# SCH_Smart_Parking_IoT_2023-05-15_2.net
KiCad netlist of a schematic drawn in EasyEDA
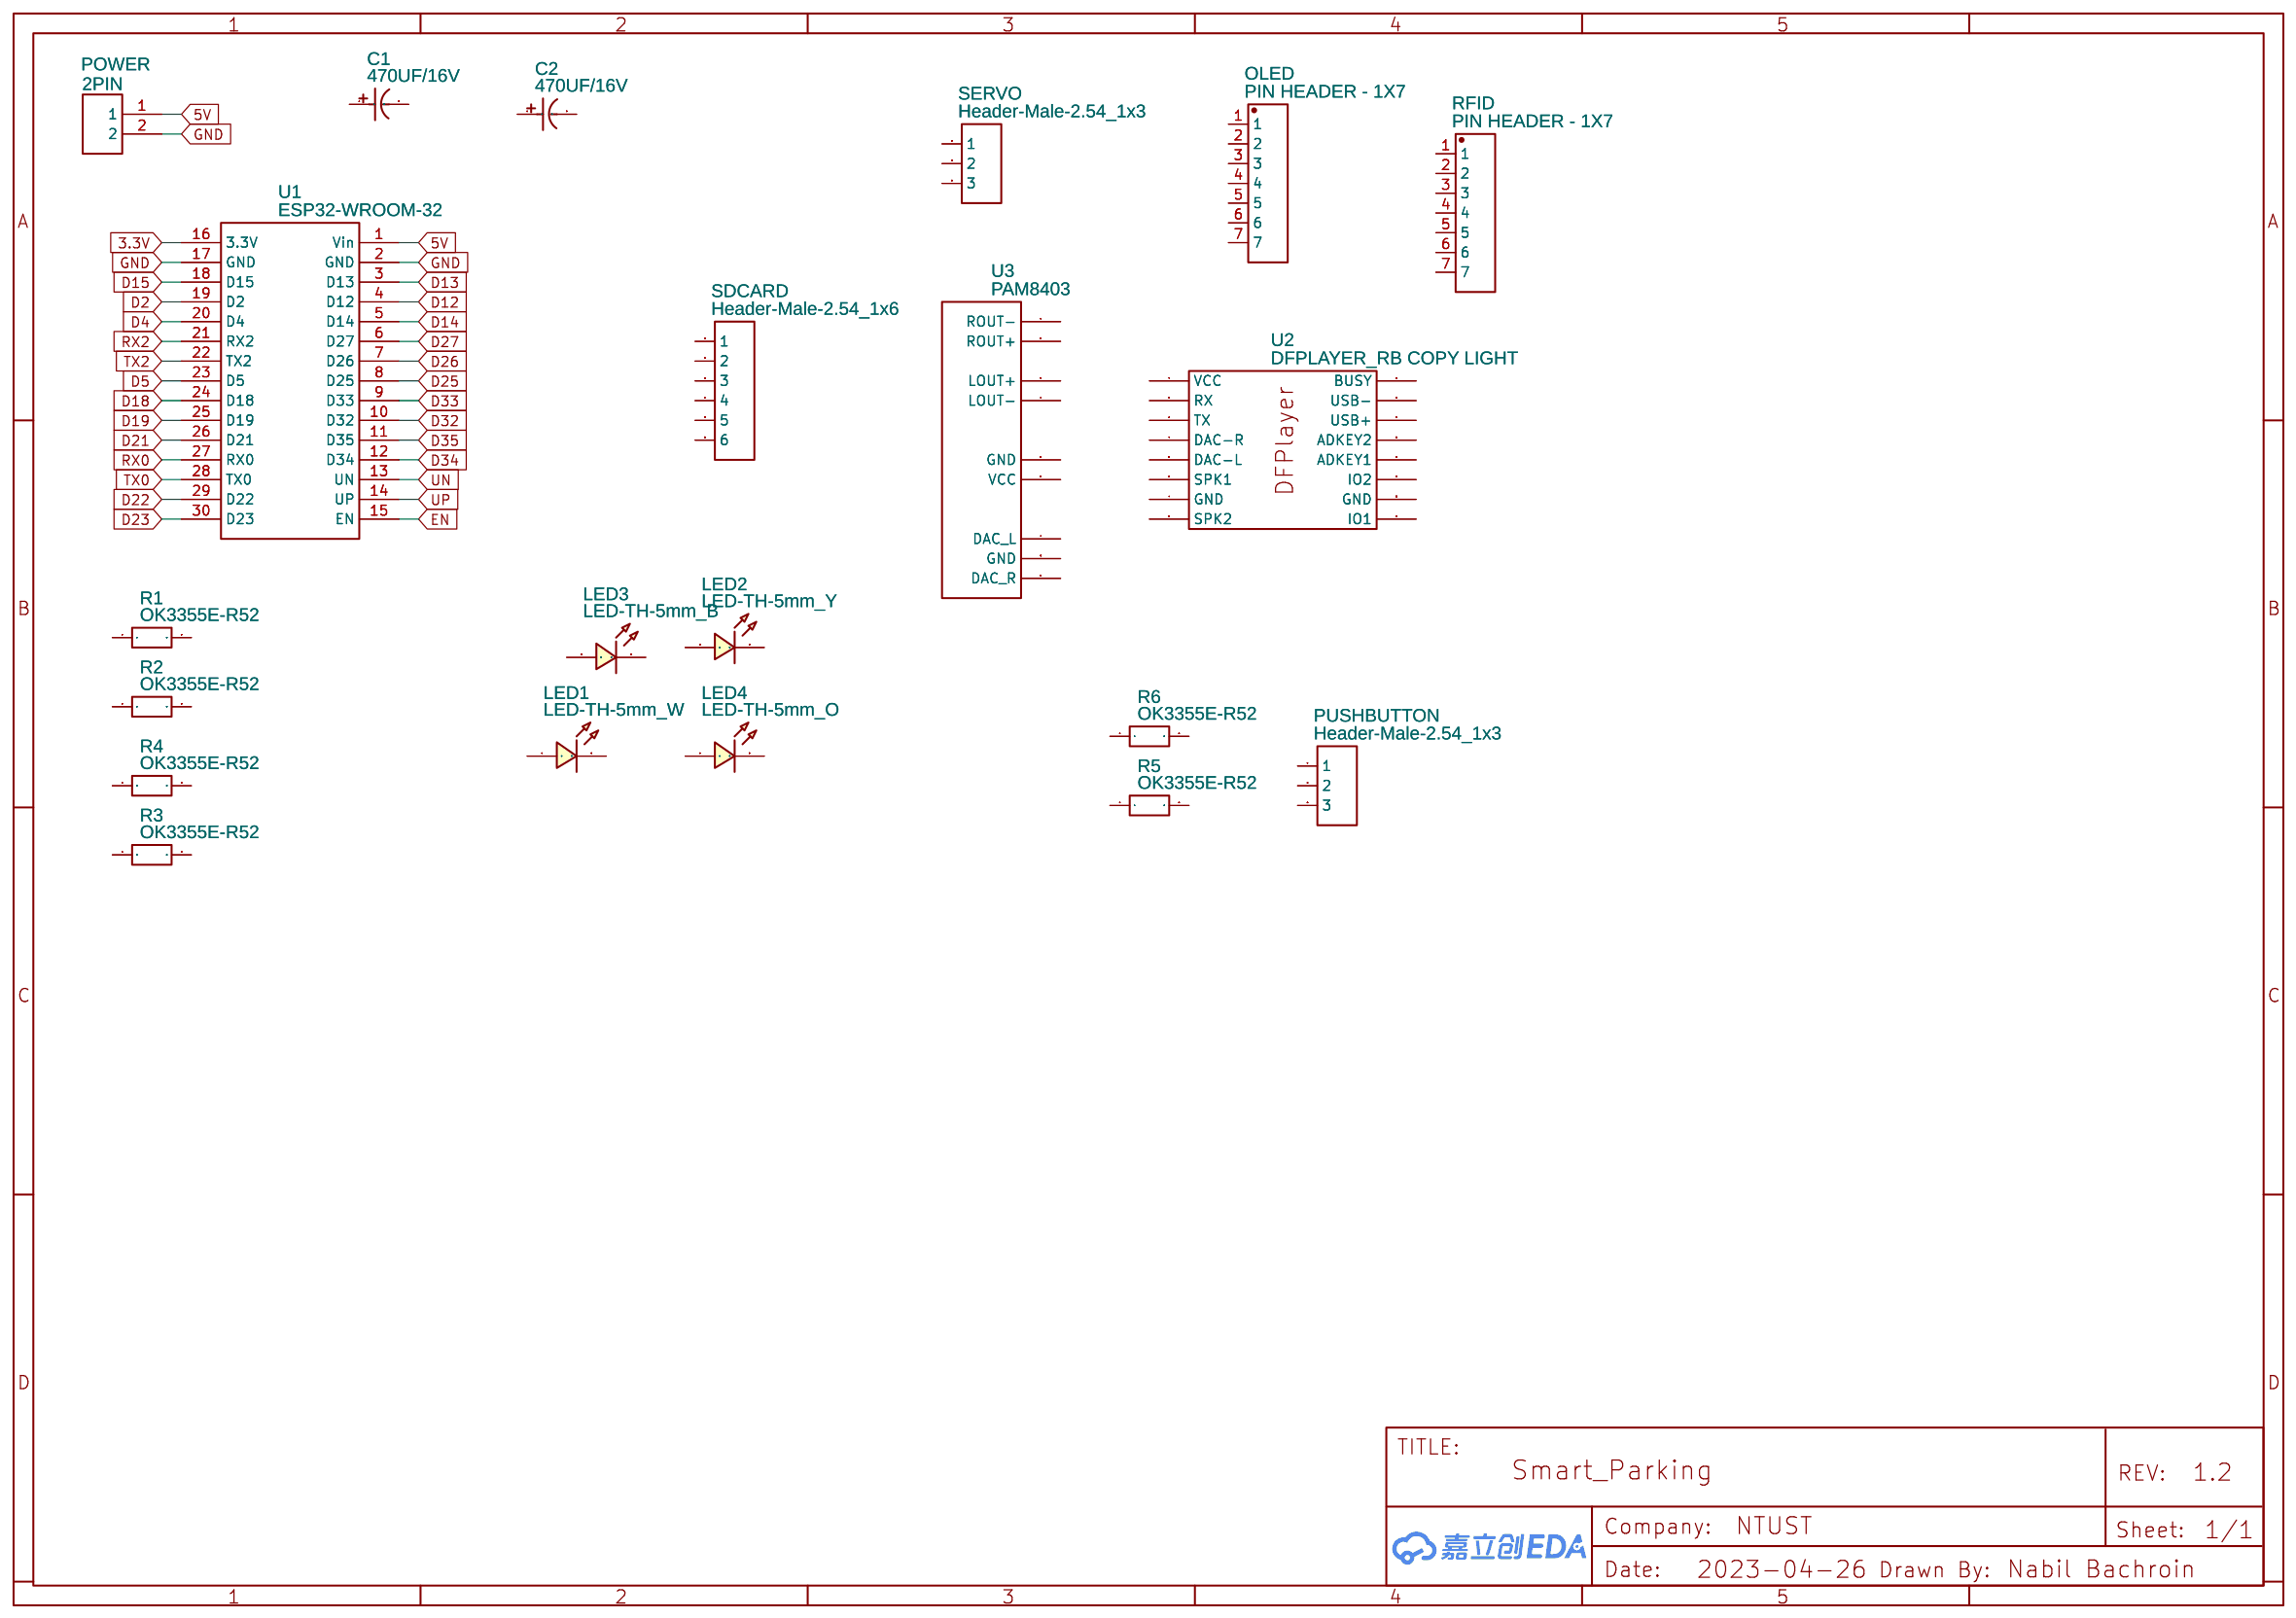
[diagram p0: schematic sheet]

(export (version "E")
  (design (tool "Eeschema 10.0.6"))
  (components
    (comp (ref "C1")
      (value "470UF/16V")
      (fields
        (field (name "BOM_Manufacturer Part") "470uF/16V")
        (field (name "BOM_Supplier Part") "C9900008131")
      )
      (libsource (lib "") (part "470UF/16V"))
    )
    (comp (ref "C2")
      (value "470UF/16V")
      (fields
        (field (name "BOM_Manufacturer Part") "470uF/16V")
        (field (name "BOM_Supplier Part") "C9900008131")
      )
      (libsource (lib "") (part "470UF/16V"))
    )
    (comp (ref "LED1") (value "LED-TH-5mm_W") (libsource (lib "") (part "LED-TH-5mm_W")))
    (comp (ref "LED2") (value "LED-TH-5mm_Y") (libsource (lib "") (part "LED-TH-5mm_Y")))
    (comp (ref "LED3") (value "LED-TH-5mm_B") (libsource (lib "") (part "LED-TH-5mm_B")))
    (comp (ref "LED4") (value "LED-TH-5mm_O") (libsource (lib "") (part "LED-TH-5mm_O")))
    (comp (ref "OLED") (value "PIN HEADER - 1X7") (libsource (lib "") (part "PIN HEADER - 1X7_1")))
    (comp (ref "POWER")
      (value "2PIN")
      (fields (field (name "BOM_Manufacturer Part") "Pin_Header_2"))
      (libsource (lib "") (part "2PIN"))
    )
    (comp (ref "PUSHBUTTON")
      (value "Header-Male-2.54_1x3")
      (fields (field (name "BOM_Manufacturer Part") "2.54-1*3P针") (field (name "BOM_Supplier Part") "C49257"))
      (libsource (lib "") (part "Header-Male-2.54_1x3"))
    )
    (comp (ref "R1")
      (value "OK3355E-R52")
      (fields (field (name "BOM_Supplier Part") "C3522642"))
      (libsource (lib "") (part "OK3355E-R52"))
    )
    (comp (ref "R2")
      (value "OK3355E-R52")
      (fields (field (name "BOM_Supplier Part") "C3522642"))
      (libsource (lib "") (part "OK3355E-R52"))
    )
    (comp (ref "R3")
      (value "OK3355E-R52")
      (fields (field (name "BOM_Supplier Part") "C3522642"))
      (libsource (lib "") (part "OK3355E-R52"))
    )
    (comp (ref "R4")
      (value "OK3355E-R52")
      (fields (field (name "BOM_Supplier Part") "C3522642"))
      (libsource (lib "") (part "OK3355E-R52"))
    )
    (comp (ref "R5")
      (value "OK3355E-R52")
      (fields (field (name "BOM_Supplier Part") "C3522642"))
      (libsource (lib "") (part "OK3355E-R52"))
    )
    (comp (ref "R6")
      (value "OK3355E-R52")
      (fields (field (name "BOM_Supplier Part") "C3522642"))
      (libsource (lib "") (part "OK3355E-R52"))
    )
    (comp (ref "RFID") (value "PIN HEADER - 1X7") (libsource (lib "") (part "PIN HEADER - 1X7")))
    (comp (ref "SDCARD")
      (value "Header-Male-2.54_1x6")
      (fields
        (field (name "BOM_Manufacturer Part") "2.54-1x6P直针")
        (field (name "BOM_Supplier Part") "C37208")
      )
      (libsource (lib "") (part "Header-Male-2.54_1x6"))
    )
    (comp (ref "SERVO")
      (value "Header-Male-2.54_1x3")
      (fields (field (name "BOM_Manufacturer Part") "2.54-1*3P针") (field (name "BOM_Supplier Part") "C49257"))
      (libsource (lib "") (part "Header-Male-2.54_1x3_1"))
    )
    (comp (ref "U1") (value "ESP32-WROOM-32") (libsource (lib "") (part "ESP32-WROOM-32")))
    (comp (ref "U2")
      (value "DFPLAYER_RB COPY LIGHT")
      (fields (field (name "BOM_Manufacturer Part") "DFPLAYER"))
      (libsource (lib "") (part "DFPLAYER_RB COPY LIGHT"))
    )
    (comp (ref "U3") (value "PAM8403") (libsource (lib "") (part "PAM8403")))
  )
  (nets
    (net (code "1") (name "3.3V") (class "Default")
      (node (ref "U1") (pin "16") (pinfunction "3.3V_16") (pintype "unspecified"))
    )
    (net (code "2") (name "5V") (class "Default")
      (node (ref "POWER") (pin "1") (pinfunction "1_1") (pintype "unspecified"))
      (node (ref "U1") (pin "1") (pinfunction "Vin_1") (pintype "unspecified"))
    )
    (net (code "3") (name "D2") (class "Default")
      (node (ref "U1") (pin "19") (pinfunction "D2_19") (pintype "unspecified"))
    )
    (net (code "4") (name "D4") (class "Default")
      (node (ref "U1") (pin "20") (pinfunction "D4_20") (pintype "unspecified"))
    )
    (net (code "5") (name "D5") (class "Default")
      (node (ref "U1") (pin "23") (pinfunction "D5_23") (pintype "unspecified"))
    )
    (net (code "6") (name "D12") (class "Default")
      (node (ref "U1") (pin "4") (pinfunction "D12_4") (pintype "unspecified"))
    )
    (net (code "7") (name "D13") (class "Default")
      (node (ref "U1") (pin "3") (pinfunction "D13_3") (pintype "unspecified"))
    )
    (net (code "8") (name "D14") (class "Default")
      (node (ref "U1") (pin "5") (pinfunction "D14_5") (pintype "unspecified"))
    )
    (net (code "9") (name "D15") (class "Default")
      (node (ref "U1") (pin "18") (pinfunction "D15_18") (pintype "unspecified"))
    )
    (net (code "10") (name "D18") (class "Default")
      (node (ref "U1") (pin "24") (pinfunction "D18_24") (pintype "unspecified"))
    )
    (net (code "11") (name "D19") (class "Default")
      (node (ref "U1") (pin "25") (pinfunction "D19_25") (pintype "unspecified"))
    )
    (net (code "12") (name "D21") (class "Default")
      (node (ref "U1") (pin "26") (pinfunction "D21_26") (pintype "unspecified"))
    )
    (net (code "13") (name "D22") (class "Default")
      (node (ref "U1") (pin "29") (pinfunction "D22_29") (pintype "unspecified"))
    )
    (net (code "14") (name "D23") (class "Default")
      (node (ref "U1") (pin "30") (pinfunction "D23_30") (pintype "unspecified"))
    )
    (net (code "15") (name "D25") (class "Default")
      (node (ref "U1") (pin "8") (pinfunction "D25_8") (pintype "unspecified"))
    )
    (net (code "16") (name "D26") (class "Default")
      (node (ref "U1") (pin "7") (pinfunction "D26_7") (pintype "unspecified"))
    )
    (net (code "17") (name "D27") (class "Default")
      (node (ref "U1") (pin "6") (pinfunction "D27_6") (pintype "unspecified"))
    )
    (net (code "18") (name "D32") (class "Default")
      (node (ref "U1") (pin "10") (pinfunction "D32_10") (pintype "unspecified"))
    )
    (net (code "19") (name "D33") (class "Default")
      (node (ref "U1") (pin "9") (pinfunction "D33_9") (pintype "unspecified"))
    )
    (net (code "20") (name "D34") (class "Default")
      (node (ref "U1") (pin "12") (pinfunction "D34_12") (pintype "unspecified"))
    )
    (net (code "21") (name "D35") (class "Default")
      (node (ref "U1") (pin "11") (pinfunction "D35_11") (pintype "unspecified"))
    )
    (net (code "22") (name "EN") (class "Default")
      (node (ref "U1") (pin "15") (pinfunction "EN_15") (pintype "unspecified"))
    )
    (net (code "23") (name "GND") (class "Default")
      (node (ref "POWER") (pin "2") (pinfunction "2_2") (pintype "unspecified"))
      (node (ref "U1") (pin "17") (pinfunction "GND_17") (pintype "unspecified"))
      (node (ref "U1") (pin "2") (pinfunction "GND_2") (pintype "unspecified"))
    )
    (net (code "24") (name "RX0") (class "Default")
      (node (ref "U1") (pin "27") (pinfunction "RX0_27") (pintype "unspecified"))
    )
    (net (code "25") (name "RX2") (class "Default")
      (node (ref "U1") (pin "21") (pinfunction "RX2_21") (pintype "unspecified"))
    )
    (net (code "26") (name "TX0") (class "Default")
      (node (ref "U1") (pin "28") (pinfunction "TX0_28") (pintype "unspecified"))
    )
    (net (code "27") (name "TX2") (class "Default")
      (node (ref "U1") (pin "22") (pinfunction "TX2_22") (pintype "unspecified"))
    )
    (net (code "28") (name "UN") (class "Default")
      (node (ref "U1") (pin "13") (pinfunction "UN_13") (pintype "unspecified"))
    )
    (net (code "29") (name "UP") (class "Default")
      (node (ref "U1") (pin "14") (pinfunction "UP_14") (pintype "unspecified"))
    )
    (net (code "30") (name "unconnected-(C1-Pad1)") (class "Default")
      (node (ref "C1") (pin "1") (pinfunction "1_1") (pintype "input"))
    )
    (net (code "31") (name "unconnected-(C1-Pad2)") (class "Default")
      (node (ref "C1") (pin "2") (pinfunction "2_2") (pintype "input"))
    )
    (net (code "32") (name "unconnected-(C2-Pad1)") (class "Default")
      (node (ref "C2") (pin "1") (pinfunction "1_1") (pintype "input"))
    )
    (net (code "33") (name "unconnected-(C2-Pad2)") (class "Default")
      (node (ref "C2") (pin "2") (pinfunction "2_2") (pintype "input"))
    )
    (net (code "34") (name "unconnected-(LED1-Pad1)") (class "Default")
      (node (ref "LED1") (pin "1") (pinfunction "1_1") (pintype "unspecified"))
    )
    (net (code "35") (name "unconnected-(LED1-Pad2)") (class "Default")
      (node (ref "LED1") (pin "2") (pinfunction "2_2") (pintype "unspecified"))
    )
    (net (code "36") (name "unconnected-(LED2-Pad1)") (class "Default")
      (node (ref "LED2") (pin "1") (pinfunction "1_1") (pintype "unspecified"))
    )
    (net (code "37") (name "unconnected-(LED2-Pad2)") (class "Default")
      (node (ref "LED2") (pin "2") (pinfunction "2_2") (pintype "unspecified"))
    )
    (net (code "38") (name "unconnected-(LED3-Pad1)") (class "Default")
      (node (ref "LED3") (pin "1") (pinfunction "1_1") (pintype "unspecified"))
    )
    (net (code "39") (name "unconnected-(LED3-Pad2)") (class "Default")
      (node (ref "LED3") (pin "2") (pinfunction "2_2") (pintype "unspecified"))
    )
    (net (code "40") (name "unconnected-(LED4-Pad1)") (class "Default")
      (node (ref "LED4") (pin "1") (pinfunction "1_1") (pintype "unspecified"))
    )
    (net (code "41") (name "unconnected-(LED4-Pad2)") (class "Default")
      (node (ref "LED4") (pin "2") (pinfunction "2_2") (pintype "unspecified"))
    )
    (net (code "42") (name "unconnected-(OLED-Pad1)") (class "Default")
      (node (ref "OLED") (pin "1") (pinfunction "1_1") (pintype "unspecified"))
    )
    (net (code "43") (name "unconnected-(OLED-Pad2)") (class "Default")
      (node (ref "OLED") (pin "2") (pinfunction "2_2") (pintype "unspecified"))
    )
    (net (code "44") (name "unconnected-(OLED-Pad3)") (class "Default")
      (node (ref "OLED") (pin "3") (pinfunction "3_3") (pintype "unspecified"))
    )
    (net (code "45") (name "unconnected-(OLED-Pad4)") (class "Default")
      (node (ref "OLED") (pin "4") (pinfunction "4_4") (pintype "unspecified"))
    )
    (net (code "46") (name "unconnected-(OLED-Pad5)") (class "Default")
      (node (ref "OLED") (pin "5") (pinfunction "5_5") (pintype "unspecified"))
    )
    (net (code "47") (name "unconnected-(OLED-Pad6)") (class "Default")
      (node (ref "OLED") (pin "6") (pinfunction "6_6") (pintype "unspecified"))
    )
    (net (code "48") (name "unconnected-(OLED-Pad7)") (class "Default")
      (node (ref "OLED") (pin "7") (pinfunction "7_7") (pintype "unspecified"))
    )
    (net (code "49") (name "unconnected-(PUSHBUTTON-Pad1)") (class "Default")
      (node (ref "PUSHBUTTON") (pin "1") (pinfunction "1_1") (pintype "input"))
    )
    (net (code "50") (name "unconnected-(PUSHBUTTON-Pad2)") (class "Default")
      (node (ref "PUSHBUTTON") (pin "2") (pinfunction "2_2") (pintype "input"))
    )
    (net (code "51") (name "unconnected-(PUSHBUTTON-Pad3)") (class "Default")
      (node (ref "PUSHBUTTON") (pin "3") (pinfunction "3_3") (pintype "input"))
    )
    (net (code "52") (name "unconnected-(R1-Pad1)") (class "Default")
      (node (ref "R1") (pin "1") (pinfunction "1_1") (pintype "unspecified"))
    )
    (net (code "53") (name "unconnected-(R1-Pad2)") (class "Default")
      (node (ref "R1") (pin "2") (pinfunction "2_2") (pintype "unspecified"))
    )
    (net (code "54") (name "unconnected-(R2-Pad1)") (class "Default")
      (node (ref "R2") (pin "1") (pinfunction "1_1") (pintype "unspecified"))
    )
    (net (code "55") (name "unconnected-(R2-Pad2)") (class "Default")
      (node (ref "R2") (pin "2") (pinfunction "2_2") (pintype "unspecified"))
    )
    (net (code "56") (name "unconnected-(R3-Pad1)") (class "Default")
      (node (ref "R3") (pin "1") (pinfunction "1_1") (pintype "unspecified"))
    )
    (net (code "57") (name "unconnected-(R3-Pad2)") (class "Default")
      (node (ref "R3") (pin "2") (pinfunction "2_2") (pintype "unspecified"))
    )
    (net (code "58") (name "unconnected-(R4-Pad1)") (class "Default")
      (node (ref "R4") (pin "1") (pinfunction "1_1") (pintype "unspecified"))
    )
    (net (code "59") (name "unconnected-(R4-Pad2)") (class "Default")
      (node (ref "R4") (pin "2") (pinfunction "2_2") (pintype "unspecified"))
    )
    (net (code "60") (name "unconnected-(R5-Pad1)") (class "Default")
      (node (ref "R5") (pin "1") (pinfunction "1_1") (pintype "unspecified"))
    )
    (net (code "61") (name "unconnected-(R5-Pad2)") (class "Default")
      (node (ref "R5") (pin "2") (pinfunction "2_2") (pintype "unspecified"))
    )
    (net (code "62") (name "unconnected-(R6-Pad1)") (class "Default")
      (node (ref "R6") (pin "1") (pinfunction "1_1") (pintype "unspecified"))
    )
    (net (code "63") (name "unconnected-(R6-Pad2)") (class "Default")
      (node (ref "R6") (pin "2") (pinfunction "2_2") (pintype "unspecified"))
    )
    (net (code "64") (name "unconnected-(RFID-Pad1)") (class "Default")
      (node (ref "RFID") (pin "1") (pinfunction "1_1") (pintype "unspecified"))
    )
    (net (code "65") (name "unconnected-(RFID-Pad2)") (class "Default")
      (node (ref "RFID") (pin "2") (pinfunction "2_2") (pintype "unspecified"))
    )
    (net (code "66") (name "unconnected-(RFID-Pad3)") (class "Default")
      (node (ref "RFID") (pin "3") (pinfunction "3_3") (pintype "unspecified"))
    )
    (net (code "67") (name "unconnected-(RFID-Pad4)") (class "Default")
      (node (ref "RFID") (pin "4") (pinfunction "4_4") (pintype "unspecified"))
    )
    (net (code "68") (name "unconnected-(RFID-Pad5)") (class "Default")
      (node (ref "RFID") (pin "5") (pinfunction "5_5") (pintype "unspecified"))
    )
    (net (code "69") (name "unconnected-(RFID-Pad6)") (class "Default")
      (node (ref "RFID") (pin "6") (pinfunction "6_6") (pintype "unspecified"))
    )
    (net (code "70") (name "unconnected-(RFID-Pad7)") (class "Default")
      (node (ref "RFID") (pin "7") (pinfunction "7_7") (pintype "unspecified"))
    )
    (net (code "71") (name "unconnected-(SDCARD-Pad1)") (class "Default")
      (node (ref "SDCARD") (pin "1") (pinfunction "1_1") (pintype "input"))
    )
    (net (code "72") (name "unconnected-(SDCARD-Pad2)") (class "Default")
      (node (ref "SDCARD") (pin "2") (pinfunction "2_2") (pintype "input"))
    )
    (net (code "73") (name "unconnected-(SDCARD-Pad3)") (class "Default")
      (node (ref "SDCARD") (pin "3") (pinfunction "3_3") (pintype "input"))
    )
    (net (code "74") (name "unconnected-(SDCARD-Pad4)") (class "Default")
      (node (ref "SDCARD") (pin "4") (pinfunction "4_4") (pintype "input"))
    )
    (net (code "75") (name "unconnected-(SDCARD-Pad5)") (class "Default")
      (node (ref "SDCARD") (pin "5") (pinfunction "5_5") (pintype "input"))
    )
    (net (code "76") (name "unconnected-(SDCARD-Pad6)") (class "Default")
      (node (ref "SDCARD") (pin "6") (pinfunction "6_6") (pintype "input"))
    )
    (net (code "77") (name "unconnected-(SERVO-Pad1)") (class "Default")
      (node (ref "SERVO") (pin "1") (pinfunction "1_1") (pintype "input"))
    )
    (net (code "78") (name "unconnected-(SERVO-Pad2)") (class "Default")
      (node (ref "SERVO") (pin "2") (pinfunction "2_2") (pintype "input"))
    )
    (net (code "79") (name "unconnected-(SERVO-Pad3)") (class "Default")
      (node (ref "SERVO") (pin "3") (pinfunction "3_3") (pintype "input"))
    )
    (net (code "80") (name "unconnected-(U2-ADKEY1-Pad12)") (class "Default")
      (node (ref "U2") (pin "12") (pinfunction "ADKEY1_12") (pintype "unspecified"))
    )
    (net (code "81") (name "unconnected-(U2-ADKEY2-Pad13)") (class "Default")
      (node (ref "U2") (pin "13") (pinfunction "ADKEY2_13") (pintype "unspecified"))
    )
    (net (code "82") (name "unconnected-(U2-BUSY-Pad16)") (class "Default")
      (node (ref "U2") (pin "16") (pinfunction "BUSY_16") (pintype "unspecified"))
    )
    (net (code "83") (name "unconnected-(U2-DAC-L-Pad5)") (class "Default")
      (node (ref "U2") (pin "5") (pinfunction "DAC-L_5") (pintype "unspecified"))
    )
    (net (code "84") (name "unconnected-(U2-DAC-R-Pad4)") (class "Default")
      (node (ref "U2") (pin "4") (pinfunction "DAC-R_4") (pintype "unspecified"))
    )
    (net (code "85") (name "unconnected-(U2-GND-Pad7)") (class "Default")
      (node (ref "U2") (pin "7") (pinfunction "GND_7") (pintype "unspecified"))
    )
    (net (code "86") (name "unconnected-(U2-GND-Pad10)") (class "Default")
      (node (ref "U2") (pin "10") (pinfunction "GND_10") (pintype "unspecified"))
    )
    (net (code "87") (name "unconnected-(U2-IO1-Pad9)") (class "Default")
      (node (ref "U2") (pin "9") (pinfunction "IO1_9") (pintype "unspecified"))
    )
    (net (code "88") (name "unconnected-(U2-IO2-Pad11)") (class "Default")
      (node (ref "U2") (pin "11") (pinfunction "IO2_11") (pintype "unspecified"))
    )
    (net (code "89") (name "unconnected-(U2-RX-Pad2)") (class "Default")
      (node (ref "U2") (pin "2") (pinfunction "RX_2") (pintype "unspecified"))
    )
    (net (code "90") (name "unconnected-(U2-SPK1-Pad6)") (class "Default")
      (node (ref "U2") (pin "6") (pinfunction "SPK1_6") (pintype "unspecified"))
    )
    (net (code "91") (name "unconnected-(U2-SPK2-Pad8)") (class "Default")
      (node (ref "U2") (pin "8") (pinfunction "SPK2_8") (pintype "unspecified"))
    )
    (net (code "92") (name "unconnected-(U2-TX-Pad3)") (class "Default")
      (node (ref "U2") (pin "3") (pinfunction "TX_3") (pintype "unspecified"))
    )
    (net (code "93") (name "unconnected-(U2-USB+-Pad14)") (class "Default")
      (node (ref "U2") (pin "14") (pinfunction "USB+_14") (pintype "unspecified"))
    )
    (net (code "94") (name "unconnected-(U2-USB--Pad15)") (class "Default")
      (node (ref "U2") (pin "15") (pinfunction "USB-_15") (pintype "unspecified"))
    )
    (net (code "95") (name "unconnected-(U2-VCC-Pad1)") (class "Default")
      (node (ref "U2") (pin "1") (pinfunction "VCC_1") (pintype "unspecified"))
    )
    (net (code "96") (name "unconnected-(U3-DAC_L-Pad7)") (class "Default")
      (node (ref "U3") (pin "7") (pinfunction "DAC_L_7") (pintype "unspecified"))
    )
    (net (code "97") (name "unconnected-(U3-DAC_R-Pad9)") (class "Default")
      (node (ref "U3") (pin "9") (pinfunction "DAC_R_9") (pintype "unspecified"))
    )
    (net (code "98") (name "unconnected-(U3-GND-Pad5)") (class "Default")
      (node (ref "U3") (pin "5") (pinfunction "GND_5") (pintype "unspecified"))
    )
    (net (code "99") (name "unconnected-(U3-GND-Pad8)") (class "Default")
      (node (ref "U3") (pin "8") (pinfunction "GND_8") (pintype "unspecified"))
    )
    (net (code "100") (name "unconnected-(U3-LOUT+-Pad3)") (class "Default")
      (node (ref "U3") (pin "3") (pinfunction "LOUT+_3") (pintype "unspecified"))
    )
    (net (code "101") (name "unconnected-(U3-LOUT--Pad4)") (class "Default")
      (node (ref "U3") (pin "4") (pinfunction "LOUT-_4") (pintype "unspecified"))
    )
    (net (code "102") (name "unconnected-(U3-ROUT+-Pad2)") (class "Default")
      (node (ref "U3") (pin "2") (pinfunction "ROUT+_2") (pintype "unspecified"))
    )
    (net (code "103") (name "unconnected-(U3-ROUT--Pad1)") (class "Default")
      (node (ref "U3") (pin "1") (pinfunction "ROUT-_1") (pintype "unspecified"))
    )
    (net (code "104") (name "unconnected-(U3-VCC-Pad6)") (class "Default")
      (node (ref "U3") (pin "6") (pinfunction "VCC_6") (pintype "unspecified"))
    )
  )
)
